# SupplyAnalog.net
KiCad netlist of a schematic drawn in Altium Designer
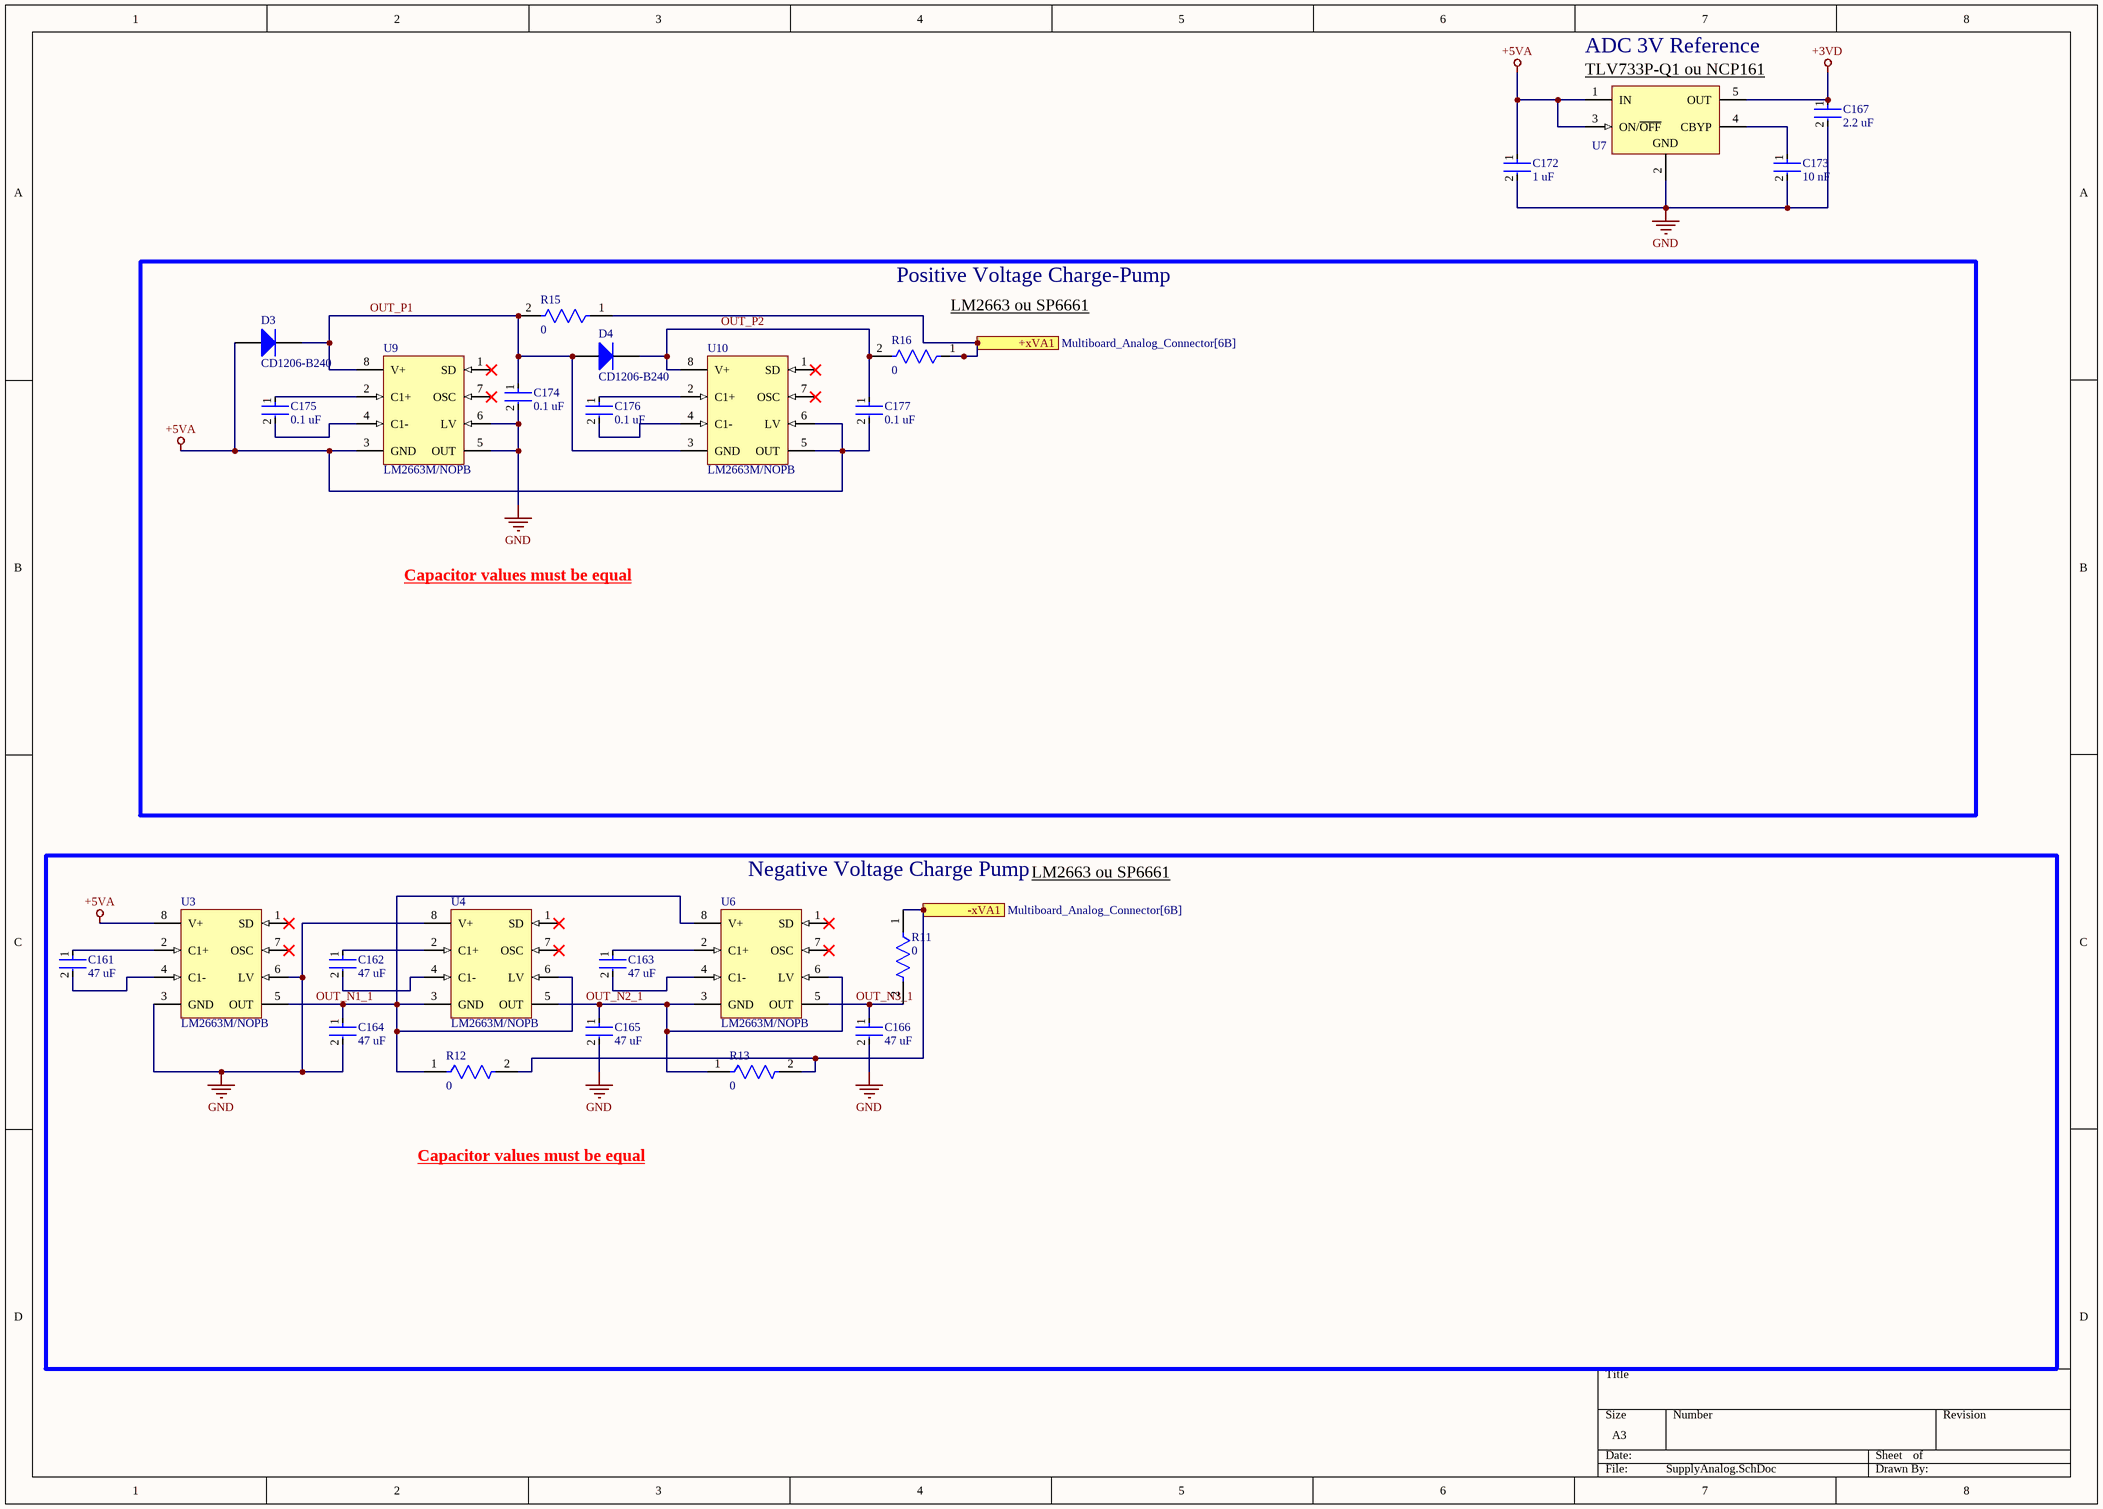
[diagram p0: SupplyAnalog.SchDoc]

(export (version "E")
  (design (tool "Eeschema 10.0.6"))
  (components
    (comp (ref "C161")
      (value "47 uF")
      (footprint "FP-CC0805-0_85-MFG")
      (description "CAP CER 0.1UF 25V X7R 0805")
      (fields (field (name "MANUFACTURER PART NUMBER") "CC0805KRX7R8BB104") (field (name "TOLERANCE") "0.1"))
      (libsource (lib "Altium Content Vault") (part "11868f565c42a9108669ba33697ecf6"))
    )
    (comp (ref "C162")
      (value "47 uF")
      (footprint "FP-CC0805-0_85-MFG")
      (description "CAP CER 0.1UF 25V X7R 0805")
      (fields (field (name "MANUFACTURER PART NUMBER") "CC0805KRX7R8BB104") (field (name "TOLERANCE") "0.1"))
      (libsource (lib "Altium Content Vault") (part "11868f565c42a9108669ba33697ecf6"))
    )
    (comp (ref "C163")
      (value "47 uF")
      (footprint "FP-CC0805-0_85-MFG")
      (description "CAP CER 0.1UF 25V X7R 0805")
      (fields (field (name "MANUFACTURER PART NUMBER") "CC0805KRX7R8BB104") (field (name "TOLERANCE") "0.1"))
      (libsource (lib "Altium Content Vault") (part "11868f565c42a9108669ba33697ecf6"))
    )
    (comp (ref "C164")
      (value "47 uF")
      (footprint "FP-CC0805-0_85-MFG")
      (description "CAP CER 0.1UF 25V X7R 0805")
      (fields (field (name "MANUFACTURER PART NUMBER") "CC0805KRX7R8BB104") (field (name "TOLERANCE") "0.1"))
      (libsource (lib "Altium Content Vault") (part "11868f565c42a9108669ba33697ecf6"))
    )
    (comp (ref "C165")
      (value "47 uF")
      (footprint "FP-CC0805-0_85-MFG")
      (description "CAP CER 0.1UF 25V X7R 0805")
      (fields (field (name "MANUFACTURER PART NUMBER") "CC0805KRX7R8BB104") (field (name "TOLERANCE") "0.1"))
      (libsource (lib "Altium Content Vault") (part "11868f565c42a9108669ba33697ecf6"))
    )
    (comp (ref "C166")
      (value "47 uF")
      (footprint "FP-CC0805-0_85-MFG")
      (description "CAP CER 0.1UF 25V X7R 0805")
      (fields (field (name "MANUFACTURER PART NUMBER") "CC0805KRX7R8BB104") (field (name "TOLERANCE") "0.1"))
      (libsource (lib "Altium Content Vault") (part "11868f565c42a9108669ba33697ecf6"))
    )
    (comp (ref "C167")
      (value "2.2 uF")
      (footprint "FP-CC0805-0_85-MFG")
      (description "CAP CER 0.1UF 25V X7R 0805")
      (fields (field (name "MANUFACTURER PART NUMBER") "CC0805KRX7R8BB104") (field (name "TOLERANCE") "0.1"))
      (libsource (lib "Altium Content Vault") (part "11868f565c42a9108669ba33697ecf6"))
    )
    (comp (ref "C172")
      (value "1 uF")
      (footprint "FP-CC0805-0_85-MFG")
      (description "CAP CER 0.1UF 25V X7R 0805")
      (fields (field (name "MANUFACTURER PART NUMBER") "CC0805KRX7R8BB104") (field (name "TOLERANCE") "0.1"))
      (libsource (lib "Altium Content Vault") (part "11868f565c42a9108669ba33697ecf6"))
    )
    (comp (ref "C173")
      (value "10 nF")
      (footprint "FP-CC0805-0_85-MFG")
      (description "CAP CER 0.1UF 25V X7R 0805")
      (fields (field (name "MANUFACTURER PART NUMBER") "CC0805KRX7R8BB104") (field (name "TOLERANCE") "0.1"))
      (libsource (lib "Altium Content Vault") (part "11868f565c42a9108669ba33697ecf6"))
    )
    (comp (ref "C174")
      (value "0.1 uF")
      (footprint "FP-CC0805-0_85-MFG")
      (description "CAP CER 0.1UF 25V X7R 0805")
      (fields (field (name "MANUFACTURER PART NUMBER") "CC0805KRX7R8BB104") (field (name "TOLERANCE") "0.1"))
      (libsource (lib "Altium Content Vault") (part "11868f565c42a9108669ba33697ecf6"))
    )
    (comp (ref "C175")
      (value "0.1 uF")
      (footprint "FP-CC0805-0_85-MFG")
      (description "CAP CER 0.1UF 25V X7R 0805")
      (fields (field (name "MANUFACTURER PART NUMBER") "CC0805KRX7R8BB104") (field (name "TOLERANCE") "0.1"))
      (libsource (lib "Altium Content Vault") (part "11868f565c42a9108669ba33697ecf6"))
    )
    (comp (ref "C176")
      (value "0.1 uF")
      (footprint "FP-CC0805-0_85-MFG")
      (description "CAP CER 0.1UF 25V X7R 0805")
      (fields (field (name "MANUFACTURER PART NUMBER") "CC0805KRX7R8BB104") (field (name "TOLERANCE") "0.1"))
      (libsource (lib "Altium Content Vault") (part "11868f565c42a9108669ba33697ecf6"))
    )
    (comp (ref "C177")
      (value "0.1 uF")
      (footprint "FP-CC0805-0_85-MFG")
      (description "CAP CER 0.1UF 25V X7R 0805")
      (fields (field (name "MANUFACTURER PART NUMBER") "CC0805KRX7R8BB104") (field (name "TOLERANCE") "0.1"))
      (libsource (lib "Altium Content Vault") (part "11868f565c42a9108669ba33697ecf6"))
    )
    (comp (ref "D3")
      (value "CD1206-B240")
      (footprint "BOUR-CD1206-S01575-2_L")
      (description "75 V Small Signal Switching Diode, 150 mA, 2.5 uA, 1026 Molded Package, RoHS, Tape and Reel")
      (fields (field (name "MANUFACTURER") "Bourns") (field (name "PARTNUMBER") "CD1206-S01575"))
      (libsource (lib "Altium Content Vault") (part "BOUR-A1K2-2"))
    )
    (comp (ref "D4")
      (value "CD1206-B240")
      (footprint "BOUR-CD1206-S01575-2_L")
      (description "75 V Small Signal Switching Diode, 150 mA, 2.5 uA, 1026 Molded Package, RoHS, Tape and Reel")
      (fields (field (name "MANUFACTURER") "Bourns") (field (name "PARTNUMBER") "CD1206-S01575"))
      (libsource (lib "Altium Content Vault") (part "BOUR-A1K2-2"))
    )
    (comp (ref "R11")
      (value "0")
      (footprint "FP-RR1220-MFG")
      (description "49.9Ω ±0.5% 0.1W 1/10W Chip Resistor 0805 (2012 Metric) Thin Film")
      (fields (field (name "TOLERANCE") "0.5%"))
      (libsource (lib "Altium Content Vault") (part "1029c3af85768c4190bb7ad29bc67b5"))
    )
    (comp (ref "R12")
      (value "0")
      (footprint "FP-RR1220-MFG")
      (description "49.9Ω ±0.5% 0.1W 1/10W Chip Resistor 0805 (2012 Metric) Thin Film")
      (fields (field (name "TOLERANCE") "0.5%"))
      (libsource (lib "Altium Content Vault") (part "1029c3af85768c4190bb7ad29bc67b5"))
    )
    (comp (ref "R13")
      (value "0")
      (footprint "FP-RR1220-MFG")
      (description "49.9Ω ±0.5% 0.1W 1/10W Chip Resistor 0805 (2012 Metric) Thin Film")
      (fields (field (name "TOLERANCE") "0.5%"))
      (libsource (lib "Altium Content Vault") (part "1029c3af85768c4190bb7ad29bc67b5"))
    )
    (comp (ref "R15")
      (value "0")
      (footprint "FP-RR1220-MFG")
      (description "49.9Ω ±0.5% 0.1W 1/10W Chip Resistor 0805 (2012 Metric) Thin Film")
      (fields (field (name "TOLERANCE") "0.5%"))
      (libsource (lib "Altium Content Vault") (part "1029c3af85768c4190bb7ad29bc67b5"))
    )
    (comp (ref "R16")
      (value "0")
      (footprint "FP-RR1220-MFG")
      (description "49.9Ω ±0.5% 0.1W 1/10W Chip Resistor 0805 (2012 Metric) Thin Film")
      (fields (field (name "TOLERANCE") "0.5%"))
      (libsource (lib "Altium Content Vault") (part "1029c3af85768c4190bb7ad29bc67b5"))
    )
    (comp (ref "U3")
      (value "LM2663M/NOPB")
      (footprint "D0008A_N")
      (description "Switched Capacitor Voltage Converter, 8-pin Narrow SOIC, Pb-Free")
      (fields (field (name "MANUFACTURER") "Texas Instruments"))
      (libsource (lib "Altium Content Vault") (part "PM-CHP-LM2661M-8"))
    )
    (comp (ref "U4")
      (value "LM2663M/NOPB")
      (footprint "D0008A_N")
      (description "Switched Capacitor Voltage Converter, 8-pin Narrow SOIC, Pb-Free")
      (fields (field (name "MANUFACTURER") "Texas Instruments"))
      (libsource (lib "Altium Content Vault") (part "PM-CHP-LM2661M-8"))
    )
    (comp (ref "U6")
      (value "LM2663M/NOPB")
      (footprint "D0008A_N")
      (description "Switched Capacitor Voltage Converter, 8-pin Narrow SOIC, Pb-Free")
      (fields (field (name "MANUFACTURER") "Texas Instruments"))
      (libsource (lib "Altium Content Vault") (part "PM-CHP-LM2661M-8"))
    )
    (comp (ref "U7")
      (value "LP2985AIM5-3.0/NOPB")
      (footprint "MF05A_L")
      (description "Micropower 150 mA Low-Noise Ultra Low-Dropout Regulator, 5-pin SOT-23, Pb-Free")
      (fields (field (name "MANUFACTURER") "National Semiconductor"))
      (libsource (lib "Altium Content Vault") (part "PM-REG-LP2985-SOT5"))
    )
    (comp (ref "U9")
      (value "LM2663M/NOPB")
      (footprint "D0008A_N")
      (description "Switched Capacitor Voltage Converter, 8-pin Narrow SOIC, Pb-Free")
      (fields (field (name "MANUFACTURER") "Texas Instruments"))
      (libsource (lib "Altium Content Vault") (part "PM-CHP-LM2661M-8"))
    )
    (comp (ref "U10")
      (value "LM2663M/NOPB")
      (footprint "D0008A_N")
      (description "Switched Capacitor Voltage Converter, 8-pin Narrow SOIC, Pb-Free")
      (fields (field (name "MANUFACTURER") "Texas Instruments"))
      (libsource (lib "Altium Content Vault") (part "PM-CHP-LM2661M-8"))
    )
  )
  (nets
    (net (code "1") (name "+3VD") (class "Default")
      (node (ref "C167") (pin "1") (pinfunction "1_1") (pintype "passive"))
      (node (ref "U7") (pin "5") (pinfunction "OUT_5") (pintype "power_in"))
    )
    (net (code "2") (name "+5VA") (class "Default")
      (node (ref "C172") (pin "1") (pinfunction "1_1") (pintype "passive"))
      (node (ref "C177") (pin "2") (pinfunction "2_2") (pintype "passive"))
      (node (ref "D3") (pin "1") (pinfunction "A_1") (pintype "passive"))
      (node (ref "U10") (pin "5") (pinfunction "OUT_5") (pintype "power_in"))
      (node (ref "U10") (pin "6") (pinfunction "LV_6") (pintype "input"))
      (node (ref "U3") (pin "8") (pinfunction "V+_8") (pintype "power_in"))
      (node (ref "U7") (pin "1") (pinfunction "IN_1") (pintype "power_in"))
      (node (ref "U7") (pin "3") (pinfunction "ON/~{OFF}_3") (pintype "input"))
      (node (ref "U9") (pin "3") (pinfunction "GND_3") (pintype "power_in"))
    )
    (net (code "3") (name "/+xVA1") (class "Default")
      (node (ref "R15") (pin "1") (pinfunction "1_1") (pintype "passive"))
      (node (ref "R16") (pin "1") (pinfunction "1_1") (pintype "passive"))
    )
    (net (code "4") (name "/-xVA1") (class "Default")
      (node (ref "R11") (pin "1") (pinfunction "1_1") (pintype "passive"))
      (node (ref "R12") (pin "2") (pinfunction "2_2") (pintype "passive"))
      (node (ref "R13") (pin "2") (pinfunction "2_2") (pintype "passive"))
    )
    (net (code "5") (name "/OUT_N1_1") (class "Default")
      (node (ref "C164") (pin "1") (pinfunction "1_1") (pintype "passive"))
      (node (ref "R12") (pin "1") (pinfunction "1_1") (pintype "passive"))
      (node (ref "U3") (pin "5") (pinfunction "OUT_5") (pintype "power_in"))
      (node (ref "U4") (pin "3") (pinfunction "GND_3") (pintype "power_in"))
      (node (ref "U4") (pin "6") (pinfunction "LV_6") (pintype "input"))
      (node (ref "U6") (pin "8") (pinfunction "V+_8") (pintype "power_in"))
    )
    (net (code "6") (name "/OUT_N2_1") (class "Default")
      (node (ref "C165") (pin "1") (pinfunction "1_1") (pintype "passive"))
      (node (ref "R13") (pin "1") (pinfunction "1_1") (pintype "passive"))
      (node (ref "U4") (pin "5") (pinfunction "OUT_5") (pintype "power_in"))
      (node (ref "U6") (pin "3") (pinfunction "GND_3") (pintype "power_in"))
      (node (ref "U6") (pin "6") (pinfunction "LV_6") (pintype "input"))
    )
    (net (code "7") (name "/OUT_N3_1") (class "Default")
      (node (ref "C166") (pin "1") (pinfunction "1_1") (pintype "passive"))
      (node (ref "R11") (pin "2") (pinfunction "2_2") (pintype "passive"))
      (node (ref "U6") (pin "5") (pinfunction "OUT_5") (pintype "power_in"))
    )
    (net (code "8") (name "/OUT_P1") (class "Default")
      (node (ref "C174") (pin "1") (pinfunction "1_1") (pintype "passive"))
      (node (ref "D3") (pin "2") (pinfunction "K_2") (pintype "passive"))
      (node (ref "D4") (pin "1") (pinfunction "A_1") (pintype "passive"))
      (node (ref "R15") (pin "2") (pinfunction "2_2") (pintype "passive"))
      (node (ref "U10") (pin "3") (pinfunction "GND_3") (pintype "power_in"))
      (node (ref "U9") (pin "8") (pinfunction "V+_8") (pintype "power_in"))
    )
    (net (code "9") (name "/OUT_P2") (class "Default")
      (node (ref "C177") (pin "1") (pinfunction "1_1") (pintype "passive"))
      (node (ref "D4") (pin "2") (pinfunction "K_2") (pintype "passive"))
      (node (ref "R16") (pin "2") (pinfunction "2_2") (pintype "passive"))
      (node (ref "U10") (pin "8") (pinfunction "V+_8") (pintype "power_in"))
    )
    (net (code "10") (name "GND") (class "Default")
      (node (ref "C164") (pin "2") (pinfunction "2_2") (pintype "passive"))
      (node (ref "C165") (pin "2") (pinfunction "2_2") (pintype "passive"))
      (node (ref "C166") (pin "2") (pinfunction "2_2") (pintype "passive"))
      (node (ref "C167") (pin "2") (pinfunction "2_2") (pintype "passive"))
      (node (ref "C172") (pin "2") (pinfunction "2_2") (pintype "passive"))
      (node (ref "C173") (pin "2") (pinfunction "2_2") (pintype "passive"))
      (node (ref "C174") (pin "2") (pinfunction "2_2") (pintype "passive"))
      (node (ref "U3") (pin "3") (pinfunction "GND_3") (pintype "power_in"))
      (node (ref "U3") (pin "6") (pinfunction "LV_6") (pintype "input"))
      (node (ref "U4") (pin "8") (pinfunction "V+_8") (pintype "power_in"))
      (node (ref "U7") (pin "2") (pinfunction "GND_2") (pintype "power_in"))
      (node (ref "U9") (pin "5") (pinfunction "OUT_5") (pintype "power_in"))
      (node (ref "U9") (pin "6") (pinfunction "LV_6") (pintype "input"))
    )
    (net (code "11") (name "Net-(U3-C1+)") (class "Default")
      (node (ref "C161") (pin "1") (pinfunction "1_1") (pintype "passive"))
      (node (ref "U3") (pin "2") (pinfunction "C1+_2") (pintype "input"))
    )
    (net (code "12") (name "Net-(U3-C1-)") (class "Default")
      (node (ref "C161") (pin "2") (pinfunction "2_2") (pintype "passive"))
      (node (ref "U3") (pin "4") (pinfunction "C1-_4") (pintype "input"))
    )
    (net (code "13") (name "Net-(U4-C1+)") (class "Default")
      (node (ref "C162") (pin "1") (pinfunction "1_1") (pintype "passive"))
      (node (ref "U4") (pin "2") (pinfunction "C1+_2") (pintype "input"))
    )
    (net (code "14") (name "Net-(U4-C1-)") (class "Default")
      (node (ref "C162") (pin "2") (pinfunction "2_2") (pintype "passive"))
      (node (ref "U4") (pin "4") (pinfunction "C1-_4") (pintype "input"))
    )
    (net (code "15") (name "Net-(U6-C1+)") (class "Default")
      (node (ref "C163") (pin "1") (pinfunction "1_1") (pintype "passive"))
      (node (ref "U6") (pin "2") (pinfunction "C1+_2") (pintype "input"))
    )
    (net (code "16") (name "Net-(U6-C1-)") (class "Default")
      (node (ref "C163") (pin "2") (pinfunction "2_2") (pintype "passive"))
      (node (ref "U6") (pin "4") (pinfunction "C1-_4") (pintype "input"))
    )
    (net (code "17") (name "Net-(U7-CBYP)") (class "Default")
      (node (ref "C173") (pin "1") (pinfunction "1_1") (pintype "passive"))
      (node (ref "U7") (pin "4") (pinfunction "CBYP_4") (pintype "passive"))
    )
    (net (code "18") (name "Net-(U9-C1+)") (class "Default")
      (node (ref "C175") (pin "1") (pinfunction "1_1") (pintype "passive"))
      (node (ref "U9") (pin "2") (pinfunction "C1+_2") (pintype "input"))
    )
    (net (code "19") (name "Net-(U9-C1-)") (class "Default")
      (node (ref "C175") (pin "2") (pinfunction "2_2") (pintype "passive"))
      (node (ref "U9") (pin "4") (pinfunction "C1-_4") (pintype "input"))
    )
    (net (code "20") (name "Net-(U10-C1+)") (class "Default")
      (node (ref "C176") (pin "1") (pinfunction "1_1") (pintype "passive"))
      (node (ref "U10") (pin "2") (pinfunction "C1+_2") (pintype "input"))
    )
    (net (code "21") (name "Net-(U10-C1-)") (class "Default")
      (node (ref "C176") (pin "2") (pinfunction "2_2") (pintype "passive"))
      (node (ref "U10") (pin "4") (pinfunction "C1-_4") (pintype "input"))
    )
    (net (code "22") (name "unconnected-(U3-OSC-Pad7)") (class "Default")
      (node (ref "U3") (pin "7") (pinfunction "OSC_7") (pintype "input+no_connect"))
    )
    (net (code "23") (name "unconnected-(U3-SD-Pad1)") (class "Default")
      (node (ref "U3") (pin "1") (pinfunction "SD_1") (pintype "input+no_connect"))
    )
    (net (code "24") (name "unconnected-(U4-OSC-Pad7)") (class "Default")
      (node (ref "U4") (pin "7") (pinfunction "OSC_7") (pintype "input+no_connect"))
    )
    (net (code "25") (name "unconnected-(U4-SD-Pad1)") (class "Default")
      (node (ref "U4") (pin "1") (pinfunction "SD_1") (pintype "input+no_connect"))
    )
    (net (code "26") (name "unconnected-(U6-OSC-Pad7)") (class "Default")
      (node (ref "U6") (pin "7") (pinfunction "OSC_7") (pintype "input+no_connect"))
    )
    (net (code "27") (name "unconnected-(U6-SD-Pad1)") (class "Default")
      (node (ref "U6") (pin "1") (pinfunction "SD_1") (pintype "input+no_connect"))
    )
    (net (code "28") (name "unconnected-(U9-OSC-Pad7)") (class "Default")
      (node (ref "U9") (pin "7") (pinfunction "OSC_7") (pintype "input+no_connect"))
    )
    (net (code "29") (name "unconnected-(U9-SD-Pad1)") (class "Default")
      (node (ref "U9") (pin "1") (pinfunction "SD_1") (pintype "input+no_connect"))
    )
    (net (code "30") (name "unconnected-(U10-OSC-Pad7)") (class "Default")
      (node (ref "U10") (pin "7") (pinfunction "OSC_7") (pintype "input+no_connect"))
    )
    (net (code "31") (name "unconnected-(U10-SD-Pad1)") (class "Default")
      (node (ref "U10") (pin "1") (pinfunction "SD_1") (pintype "input+no_connect"))
    )
  )
)
